# bicyclelab-charger-protection-2.net
KiCad netlist of a schematic drawn in EAGLE
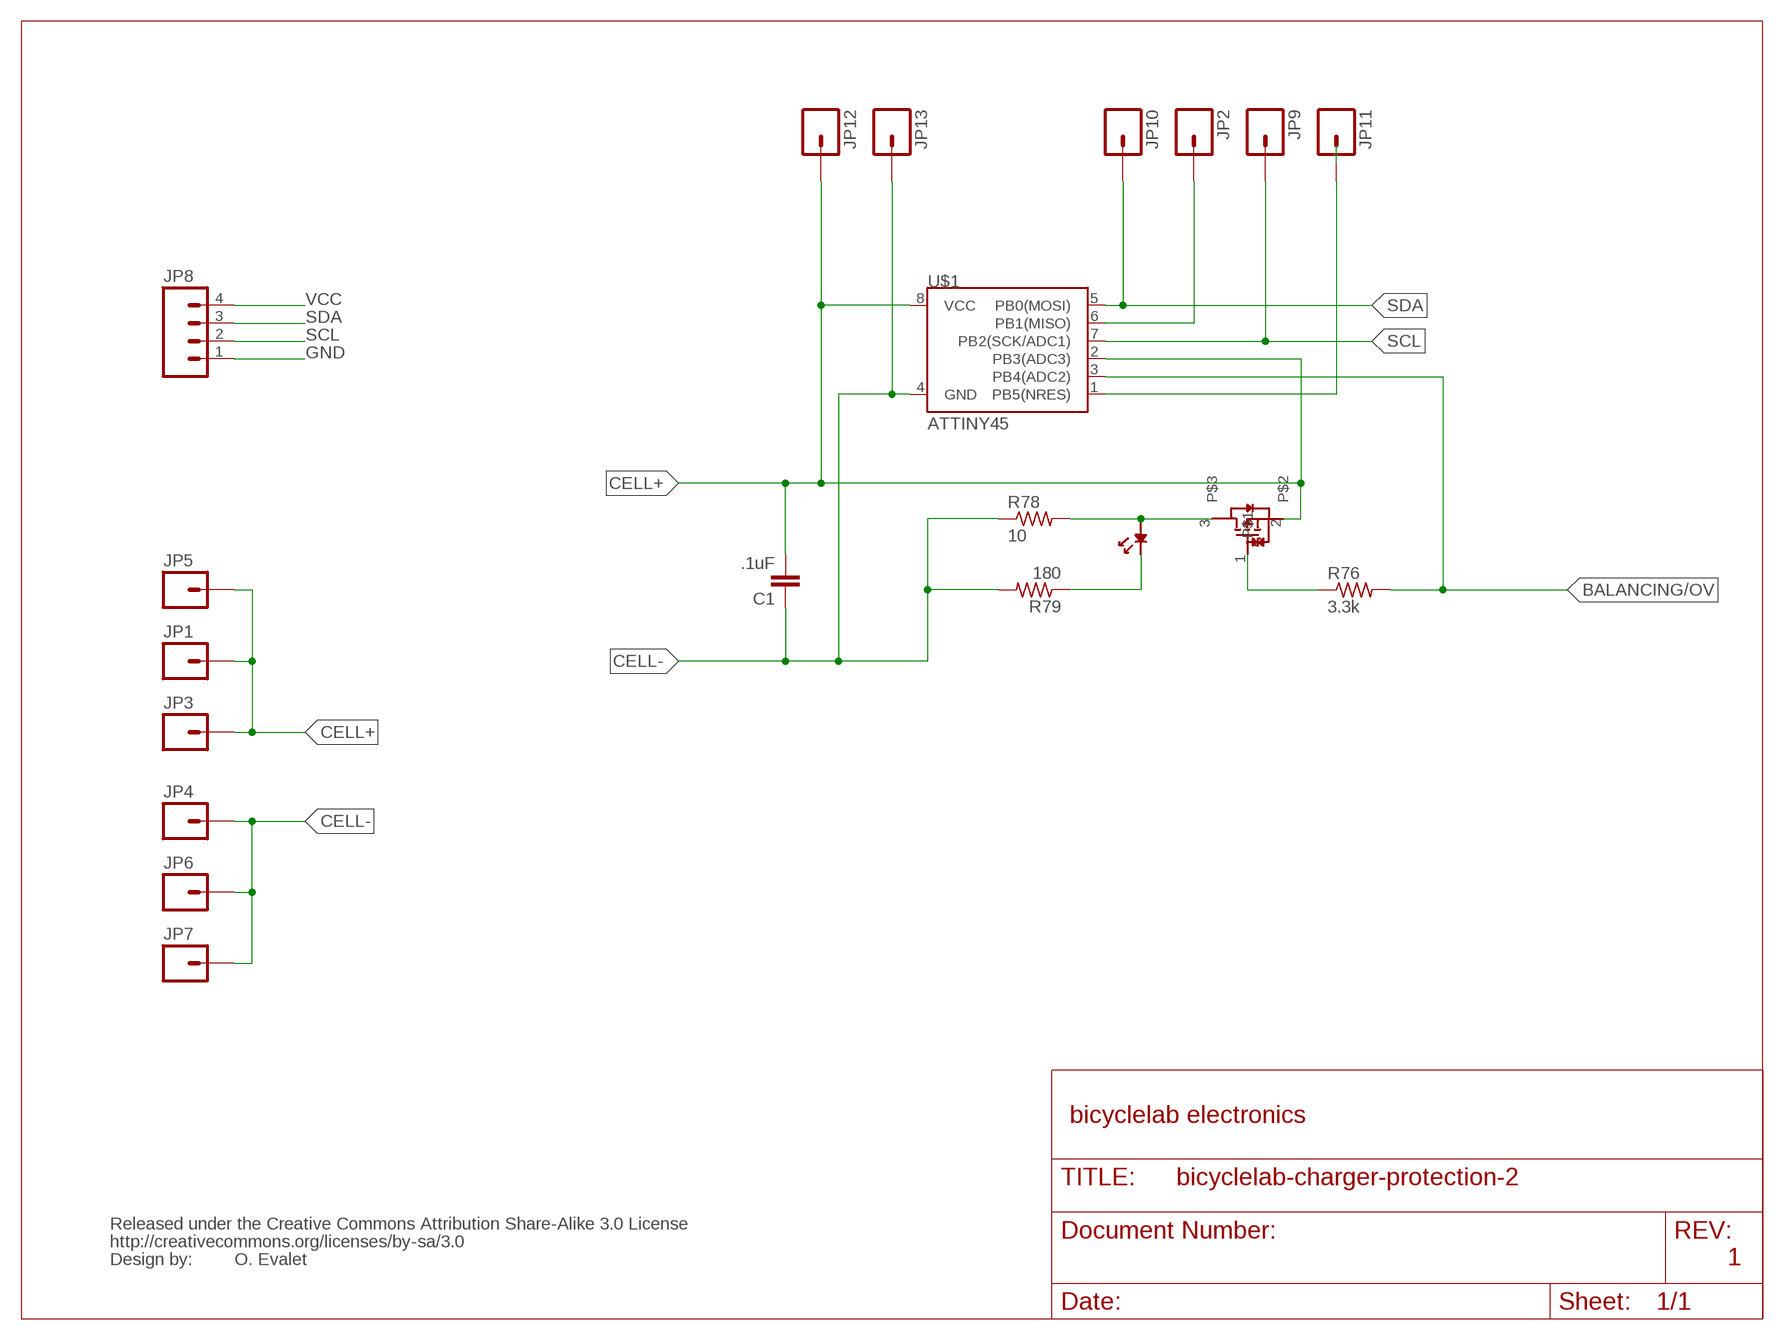
[diagram p0: schematic, sheet 1]

(export (version "E")
  (design (tool "Eeschema 10.0.6"))
  (components
    (comp (ref "C1")
      (value ".1uF")
      (footprint "eagle-import:C0402")
      (libsource (lib "eagle-import") (part "C-EUC0402"))
    )
    (comp (ref "JP1")
      (value "M01SMD-4.5X1.5")
      (footprint "eagle-import:PAD-1.5X4.5")
      (libsource (lib "eagle-import") (part "M01SMD-4.5X1.5"))
    )
    (comp (ref "JP2")
      (value "M01SMD-TINY")
      (footprint "eagle-import:PAD-SMD")
      (libsource (lib "eagle-import") (part "M01SMD-TINY"))
    )
    (comp (ref "JP3")
      (value "M01SMD-4.5X1.5")
      (footprint "eagle-import:PAD-1.5X4.5")
      (libsource (lib "eagle-import") (part "M01SMD-4.5X1.5"))
    )
    (comp (ref "JP4")
      (value "M01SMD-4.5X1.5")
      (footprint "eagle-import:PAD-1.5X4.5")
      (libsource (lib "eagle-import") (part "M01SMD-4.5X1.5"))
    )
    (comp (ref "JP5")
      (value "M01SMD-4.5X1.5")
      (footprint "eagle-import:PAD-1.5X4.5")
      (libsource (lib "eagle-import") (part "M01SMD-4.5X1.5"))
    )
    (comp (ref "JP6")
      (value "M01SMD-4.5X1.5")
      (footprint "eagle-import:PAD-1.5X4.5")
      (libsource (lib "eagle-import") (part "M01SMD-4.5X1.5"))
    )
    (comp (ref "JP7")
      (value "M01SMD-4.5X1.5")
      (footprint "eagle-import:PAD-1.5X4.5")
      (libsource (lib "eagle-import") (part "M01SMD-4.5X1.5"))
    )
    (comp (ref "JP8")
      (value "M04PTH")
      (footprint "eagle-import:1X04")
      (libsource (lib "eagle-import") (part "M04PTH"))
    )
    (comp (ref "JP9")
      (value "M01SMD-TINY")
      (footprint "eagle-import:PAD-SMD")
      (libsource (lib "eagle-import") (part "M01SMD-TINY"))
    )
    (comp (ref "JP10")
      (value "M01SMD-TINY")
      (footprint "eagle-import:PAD-SMD")
      (libsource (lib "eagle-import") (part "M01SMD-TINY"))
    )
    (comp (ref "JP11")
      (value "M01SMD-TINY")
      (footprint "eagle-import:PAD-SMD")
      (libsource (lib "eagle-import") (part "M01SMD-TINY"))
    )
    (comp (ref "JP12")
      (value "M01SMD-TINY")
      (footprint "eagle-import:PAD-SMD")
      (libsource (lib "eagle-import") (part "M01SMD-TINY"))
    )
    (comp (ref "JP13")
      (value "M01SMD-TINY")
      (footprint "eagle-import:PAD-SMD")
      (libsource (lib "eagle-import") (part "M01SMD-TINY"))
    )
    (comp (ref "LED12")
      (value "LED-0805")
      (footprint "eagle-import:0805")
      (libsource (lib "eagle-import") (part "LED-0805"))
    )
    (comp (ref "R76")
      (value "3.3k")
      (footprint "eagle-import:R0805")
      (libsource (lib "eagle-import") (part "R-US_R0805"))
    )
    (comp (ref "R78")
      (value "10")
      (footprint "eagle-import:R2512")
      (libsource (lib "eagle-import") (part "R-US_R2512"))
    )
    (comp (ref "R79")
      (value "180")
      (footprint "eagle-import:R0805")
      (libsource (lib "eagle-import") (part "R-US_R0805"))
    )
    (comp (ref "T12")
      (value "RTR020P02")
      (footprint "eagle-import:TSMT3")
      (libsource (lib "eagle-import") (part "RTR020P02"))
    )
    (comp (ref "U$1")
      (value "ATTINY45")
      (footprint "eagle-import:SO08-EIAJ")
      (libsource (lib "eagle-import") (part "ATTINY45"))
    )
    (comp (ref "U$5")
      (value "CREATIVE_COMMONS")
      (footprint "eagle-import:CREATIVE_COMMONS")
      (libsource (lib "eagle-import") (part "CREATIVE_COMMONS"))
    )
  )
  (nets
    (net (code "1") (name "/GND") (class "Default")
      (node (ref "JP8") (pin "1") (pinfunction "1_1") (pintype "passive"))
    )
    (net (code "2") (name "/VCC") (class "Default")
      (node (ref "JP8") (pin "4") (pinfunction "4_4") (pintype "passive"))
    )
    (net (code "3") (name "BALANCING{slash}OV") (class "Default")
      (node (ref "R76") (pin "2") (pinfunction "2_2") (pintype "passive"))
      (node (ref "U$1") (pin "3") (pinfunction "PB4(ADC2)_3") (pintype "bidirectional"))
    )
    (net (code "4") (name "CELL+") (class "Default")
      (node (ref "C1") (pin "2") (pinfunction "2_2") (pintype "passive"))
      (node (ref "JP1") (pin "P$1") (pinfunction "1_P$1") (pintype "passive"))
      (node (ref "JP12") (pin "P$1") (pinfunction "1_P$1") (pintype "passive"))
      (node (ref "JP3") (pin "P$1") (pinfunction "1_P$1") (pintype "passive"))
      (node (ref "JP5") (pin "P$1") (pinfunction "1_P$1") (pintype "passive"))
      (node (ref "T12") (pin "2") (pinfunction "P$2_2") (pintype "passive"))
      (node (ref "U$1") (pin "2") (pinfunction "PB3(ADC3)_2") (pintype "bidirectional"))
      (node (ref "U$1") (pin "8") (pinfunction "VCC_8") (pintype "bidirectional"))
    )
    (net (code "5") (name "CELL-") (class "Default")
      (node (ref "C1") (pin "1") (pinfunction "1_1") (pintype "passive"))
      (node (ref "JP13") (pin "P$1") (pinfunction "1_P$1") (pintype "passive"))
      (node (ref "JP4") (pin "P$1") (pinfunction "1_P$1") (pintype "passive"))
      (node (ref "JP6") (pin "P$1") (pinfunction "1_P$1") (pintype "passive"))
      (node (ref "JP7") (pin "P$1") (pinfunction "1_P$1") (pintype "passive"))
      (node (ref "R78") (pin "1") (pinfunction "1_1") (pintype "passive"))
      (node (ref "R79") (pin "2") (pinfunction "2_2") (pintype "passive"))
      (node (ref "U$1") (pin "4") (pinfunction "GND_4") (pintype "bidirectional"))
    )
    (net (code "6") (name "Net-(JP2-1)") (class "Default")
      (node (ref "JP2") (pin "P$1") (pinfunction "1_P$1") (pintype "passive"))
      (node (ref "U$1") (pin "6") (pinfunction "PB1(MISO)_6") (pintype "bidirectional"))
    )
    (net (code "7") (name "Net-(JP11-1)") (class "Default")
      (node (ref "JP11") (pin "P$1") (pinfunction "1_P$1") (pintype "passive"))
      (node (ref "U$1") (pin "1") (pinfunction "PB5(NRES)_1") (pintype "bidirectional"))
    )
    (net (code "8") (name "Net-(LED12-PadP$1)") (class "Default")
      (node (ref "LED12") (pin "P$1") (pinfunction "P$1_P$1") (pintype "passive"))
      (node (ref "R79") (pin "1") (pinfunction "1_1") (pintype "passive"))
    )
    (net (code "9") (name "Net-(T12-P$1)") (class "Default")
      (node (ref "R76") (pin "1") (pinfunction "1_1") (pintype "passive"))
      (node (ref "T12") (pin "1") (pinfunction "P$1_1") (pintype "passive"))
    )
    (net (code "10") (name "Net-(T12-P$3)") (class "Default")
      (node (ref "LED12") (pin "P$2") (pinfunction "P$2_P$2") (pintype "passive"))
      (node (ref "R78") (pin "2") (pinfunction "2_2") (pintype "passive"))
      (node (ref "T12") (pin "3") (pinfunction "P$3_3") (pintype "passive"))
    )
    (net (code "11") (name "SCL") (class "Default")
      (node (ref "JP8") (pin "2") (pinfunction "2_2") (pintype "passive"))
      (node (ref "JP9") (pin "P$1") (pinfunction "1_P$1") (pintype "passive"))
      (node (ref "U$1") (pin "7") (pinfunction "PB2(SCK/ADC1)_7") (pintype "bidirectional"))
    )
    (net (code "12") (name "SDA") (class "Default")
      (node (ref "JP10") (pin "P$1") (pinfunction "1_P$1") (pintype "passive"))
      (node (ref "JP8") (pin "3") (pinfunction "3_3") (pintype "passive"))
      (node (ref "U$1") (pin "5") (pinfunction "PB0(MOSI)_5") (pintype "bidirectional"))
    )
  )
)
